# M961.net
KiCad netlist of a schematic drawn in EAGLE
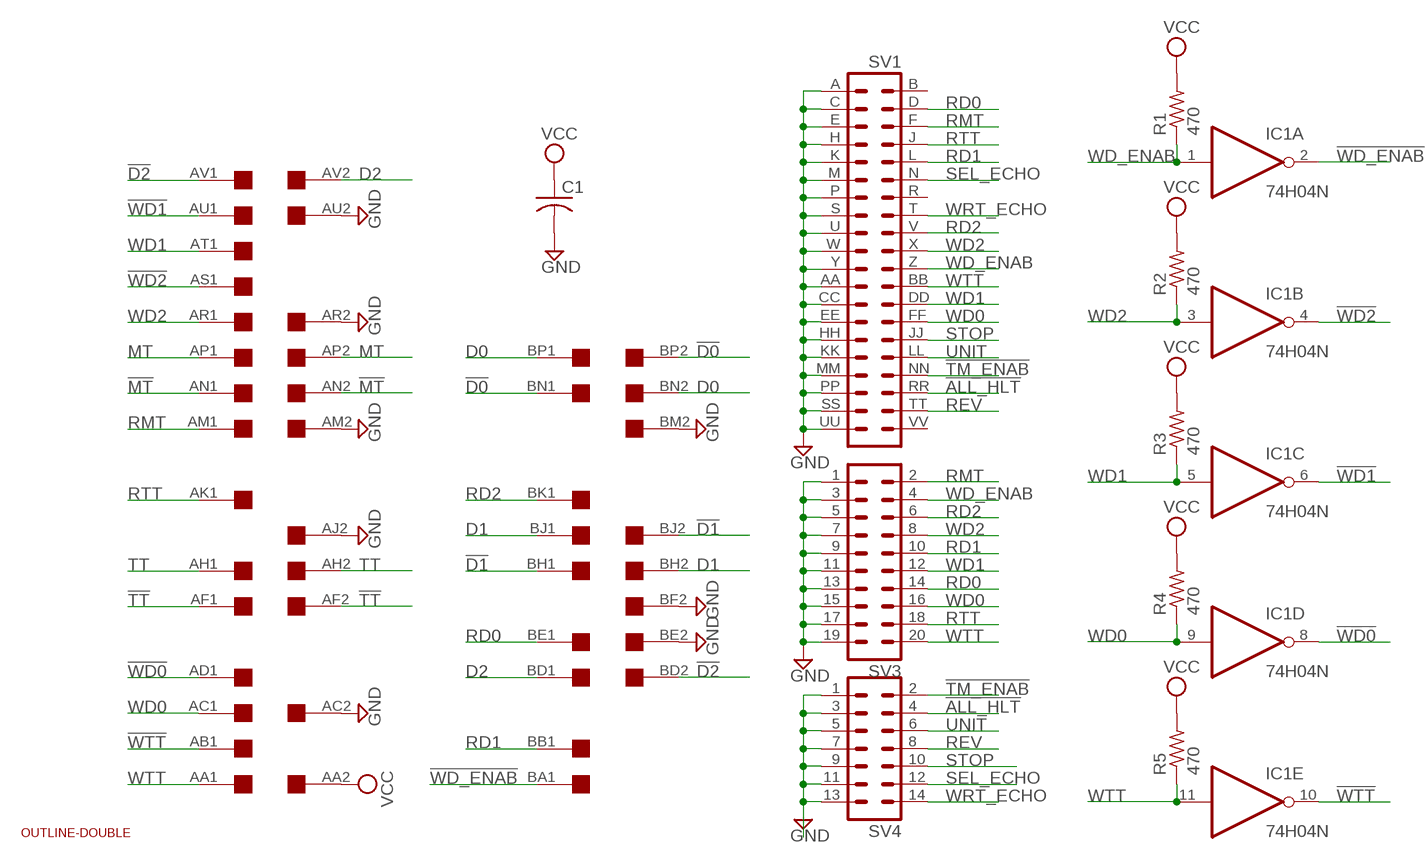
[diagram p0: schematic, sheet 1]

(export (version "E")
  (design (tool "Eeschema 10.0.6"))
  (components
    (comp (ref "C1")
      (value "C-US050-025X075")
      (footprint "eagle-import:C050-025X075")
      (libsource (lib "eagle-import") (part "C-US050-025X075"))
    )
    (comp (ref "EDGE$1")
      (value "DOUBLE")
      (footprint "eagle-import:EDGE-CON4")
      (libsource (lib "eagle-import") (part "DOUBLE"))
    )
    (comp (ref "IC1")
      (value "74H04N")
      (footprint "eagle-import:DIL14")
      (libsource (lib "eagle-import") (part "7404N"))
    )
    (comp (ref "R1")
      (value "470")
      (footprint "eagle-import:0207_10")
      (libsource (lib "eagle-import") (part "R-US_0207/10"))
    )
    (comp (ref "R2")
      (value "470")
      (footprint "eagle-import:0207_10")
      (libsource (lib "eagle-import") (part "R-US_0207/10"))
    )
    (comp (ref "R3")
      (value "470")
      (footprint "eagle-import:0207_10")
      (libsource (lib "eagle-import") (part "R-US_0207/10"))
    )
    (comp (ref "R4")
      (value "470")
      (footprint "eagle-import:0207_10")
      (libsource (lib "eagle-import") (part "R-US_0207/10"))
    )
    (comp (ref "R5")
      (value "470")
      (footprint "eagle-import:0207_10")
      (libsource (lib "eagle-import") (part "R-US_0207/10"))
    )
    (comp (ref "SV1")
      (value "DEC40PINV")
      (footprint "eagle-import:DEC40PINV")
      (libsource (lib "eagle-import") (part "DEC40PINV"))
    )
    (comp (ref "SV3")
      (value "MA10-2")
      (footprint "eagle-import:MA10-2")
      (libsource (lib "eagle-import") (part "MA10-2"))
    )
    (comp (ref "SV4")
      (value "MA07-2")
      (footprint "eagle-import:MA07-2")
      (libsource (lib "eagle-import") (part "MA07-2"))
    )
    (comp (ref "U$2")
      (value "OUTLINE-DOUBLE")
      (footprint "eagle-import:DOUBLE")
      (libsource (lib "eagle-import") (part "OUTLINE-DOUBLE"))
    )
  )
  (nets
    (net (code "1") (name "/D0") (class "Default")
      (node (ref "EDGE$1") (pin "BN2") (pinfunction "1_BN2") (pintype "bidirectional"))
      (node (ref "EDGE$1") (pin "BP1") (pinfunction "1_BP1") (pintype "bidirectional"))
    )
    (net (code "2") (name "/D1") (class "Default")
      (node (ref "EDGE$1") (pin "BH2") (pinfunction "1_BH2") (pintype "bidirectional"))
      (node (ref "EDGE$1") (pin "BJ1") (pinfunction "1_BJ1") (pintype "bidirectional"))
    )
    (net (code "3") (name "/D2") (class "Default")
      (node (ref "EDGE$1") (pin "AV2") (pinfunction "1_AV2") (pintype "bidirectional"))
      (node (ref "EDGE$1") (pin "BD1") (pinfunction "1_BD1") (pintype "bidirectional"))
    )
    (net (code "4") (name "/MT") (class "Default")
      (node (ref "EDGE$1") (pin "AP1") (pinfunction "1_AP1") (pintype "bidirectional"))
      (node (ref "EDGE$1") (pin "AP2") (pinfunction "1_AP2") (pintype "bidirectional"))
    )
    (net (code "5") (name "/RD0") (class "Default")
      (node (ref "EDGE$1") (pin "BE1") (pinfunction "1_BE1") (pintype "bidirectional"))
      (node (ref "SV1") (pin "D") (pinfunction "4_D") (pintype "bidirectional"))
      (node (ref "SV3") (pin "14") (pinfunction "14_14") (pintype "passive"))
    )
    (net (code "6") (name "/RD1") (class "Default")
      (node (ref "EDGE$1") (pin "BB1") (pinfunction "1_BB1") (pintype "bidirectional"))
      (node (ref "SV1") (pin "L") (pinfunction "10_L") (pintype "bidirectional"))
      (node (ref "SV3") (pin "10") (pinfunction "10_10") (pintype "passive"))
    )
    (net (code "7") (name "/RD2") (class "Default")
      (node (ref "EDGE$1") (pin "BK1") (pinfunction "1_BK1") (pintype "bidirectional"))
      (node (ref "SV1") (pin "V") (pinfunction "18_V") (pintype "bidirectional"))
      (node (ref "SV3") (pin "6") (pinfunction "6_6") (pintype "passive"))
    )
    (net (code "8") (name "/REV") (class "Default")
      (node (ref "SV1") (pin "TT") (pinfunction "38_TT") (pintype "bidirectional"))
      (node (ref "SV4") (pin "8") (pinfunction "8_8") (pintype "passive"))
    )
    (net (code "9") (name "/RMT") (class "Default")
      (node (ref "EDGE$1") (pin "AM1") (pinfunction "1_AM1") (pintype "bidirectional"))
      (node (ref "SV1") (pin "F") (pinfunction "6_F") (pintype "bidirectional"))
      (node (ref "SV3") (pin "2") (pinfunction "2_2") (pintype "passive"))
    )
    (net (code "10") (name "/RTT") (class "Default")
      (node (ref "EDGE$1") (pin "AK1") (pinfunction "1_AK1") (pintype "bidirectional"))
      (node (ref "SV1") (pin "J") (pinfunction "8_J") (pintype "bidirectional"))
      (node (ref "SV3") (pin "18") (pinfunction "18_18") (pintype "passive"))
    )
    (net (code "11") (name "/SEL_ECHO") (class "Default")
      (node (ref "SV1") (pin "N") (pinfunction "12_N") (pintype "bidirectional"))
      (node (ref "SV4") (pin "12") (pinfunction "12_12") (pintype "passive"))
    )
    (net (code "12") (name "/STOP") (class "Default")
      (node (ref "SV1") (pin "JJ") (pinfunction "30_JJ") (pintype "bidirectional"))
      (node (ref "SV4") (pin "10") (pinfunction "10_10") (pintype "passive"))
    )
    (net (code "13") (name "/TT") (class "Default")
      (node (ref "EDGE$1") (pin "AH1") (pinfunction "1_AH1") (pintype "bidirectional"))
      (node (ref "EDGE$1") (pin "AH2") (pinfunction "1_AH2") (pintype "bidirectional"))
    )
    (net (code "14") (name "/UNIT") (class "Default")
      (node (ref "SV1") (pin "LL") (pinfunction "32_LL") (pintype "bidirectional"))
      (node (ref "SV4") (pin "6") (pinfunction "6_6") (pintype "passive"))
    )
    (net (code "15") (name "/WD0") (class "Default")
      (node (ref "EDGE$1") (pin "AC1") (pinfunction "1_AC1") (pintype "bidirectional"))
      (node (ref "IC1") (pin "9") (pinfunction "I_9") (pintype "input"))
      (node (ref "R4") (pin "1") (pinfunction "1_1") (pintype "passive"))
      (node (ref "SV1") (pin "FF") (pinfunction "28_FF") (pintype "bidirectional"))
      (node (ref "SV3") (pin "16") (pinfunction "16_16") (pintype "passive"))
    )
    (net (code "16") (name "/WD1") (class "Default")
      (node (ref "EDGE$1") (pin "AT1") (pinfunction "1_AT1") (pintype "bidirectional"))
      (node (ref "IC1") (pin "5") (pinfunction "I_5") (pintype "input"))
      (node (ref "R3") (pin "1") (pinfunction "1_1") (pintype "passive"))
      (node (ref "SV1") (pin "DD") (pinfunction "26_DD") (pintype "bidirectional"))
      (node (ref "SV3") (pin "12") (pinfunction "12_12") (pintype "passive"))
    )
    (net (code "17") (name "/WD2") (class "Default")
      (node (ref "EDGE$1") (pin "AR1") (pinfunction "1_AR1") (pintype "bidirectional"))
      (node (ref "IC1") (pin "3") (pinfunction "I_3") (pintype "input"))
      (node (ref "R2") (pin "1") (pinfunction "1_1") (pintype "passive"))
      (node (ref "SV1") (pin "X") (pinfunction "20_X") (pintype "bidirectional"))
      (node (ref "SV3") (pin "8") (pinfunction "8_8") (pintype "passive"))
    )
    (net (code "18") (name "/WD_ENAB") (class "Default")
      (node (ref "IC1") (pin "1") (pinfunction "I_1") (pintype "input"))
      (node (ref "R1") (pin "1") (pinfunction "1_1") (pintype "passive"))
      (node (ref "SV1") (pin "Z") (pinfunction "22_Z") (pintype "bidirectional"))
      (node (ref "SV3") (pin "4") (pinfunction "4_4") (pintype "passive"))
    )
    (net (code "19") (name "/WRT_ECHO") (class "Default")
      (node (ref "SV1") (pin "T") (pinfunction "16_T") (pintype "bidirectional"))
      (node (ref "SV4") (pin "14") (pinfunction "14_14") (pintype "passive"))
    )
    (net (code "20") (name "/WTT") (class "Default")
      (node (ref "EDGE$1") (pin "AA1") (pinfunction "1_AA1") (pintype "bidirectional"))
      (node (ref "IC1") (pin "11") (pinfunction "I_11") (pintype "input"))
      (node (ref "R5") (pin "1") (pinfunction "1_1") (pintype "passive"))
      (node (ref "SV1") (pin "BB") (pinfunction "24_BB") (pintype "bidirectional"))
      (node (ref "SV3") (pin "20") (pinfunction "20_20") (pintype "passive"))
    )
    (net (code "21") (name "/~{ALL_HLT}") (class "Default")
      (node (ref "SV1") (pin "RR") (pinfunction "36_RR") (pintype "bidirectional"))
      (node (ref "SV4") (pin "4") (pinfunction "4_4") (pintype "passive"))
    )
    (net (code "22") (name "/~{D0}") (class "Default")
      (node (ref "EDGE$1") (pin "BN1") (pinfunction "1_BN1") (pintype "bidirectional"))
      (node (ref "EDGE$1") (pin "BP2") (pinfunction "1_BP2") (pintype "bidirectional"))
    )
    (net (code "23") (name "/~{D1}") (class "Default")
      (node (ref "EDGE$1") (pin "BH1") (pinfunction "1_BH1") (pintype "bidirectional"))
      (node (ref "EDGE$1") (pin "BJ2") (pinfunction "1_BJ2") (pintype "bidirectional"))
    )
    (net (code "24") (name "/~{D2}") (class "Default")
      (node (ref "EDGE$1") (pin "AV1") (pinfunction "1_AV1") (pintype "bidirectional"))
      (node (ref "EDGE$1") (pin "BD2") (pinfunction "1_BD2") (pintype "bidirectional"))
    )
    (net (code "25") (name "/~{MT}") (class "Default")
      (node (ref "EDGE$1") (pin "AN1") (pinfunction "1_AN1") (pintype "bidirectional"))
      (node (ref "EDGE$1") (pin "AN2") (pinfunction "1_AN2") (pintype "bidirectional"))
    )
    (net (code "26") (name "/~{TM_ENAB}") (class "Default")
      (node (ref "SV1") (pin "NN") (pinfunction "34_NN") (pintype "bidirectional"))
      (node (ref "SV4") (pin "2") (pinfunction "2_2") (pintype "passive"))
    )
    (net (code "27") (name "/~{TT}") (class "Default")
      (node (ref "EDGE$1") (pin "AF1") (pinfunction "1_AF1") (pintype "bidirectional"))
      (node (ref "EDGE$1") (pin "AF2") (pinfunction "1_AF2") (pintype "bidirectional"))
    )
    (net (code "28") (name "/~{WD0}") (class "Default")
      (node (ref "EDGE$1") (pin "AD1") (pinfunction "1_AD1") (pintype "bidirectional"))
      (node (ref "IC1") (pin "8") (pinfunction "O_8") (pintype "output"))
    )
    (net (code "29") (name "/~{WD1}") (class "Default")
      (node (ref "EDGE$1") (pin "AU1") (pinfunction "1_AU1") (pintype "bidirectional"))
      (node (ref "IC1") (pin "6") (pinfunction "O_6") (pintype "output"))
    )
    (net (code "30") (name "/~{WD2}") (class "Default")
      (node (ref "EDGE$1") (pin "AS1") (pinfunction "1_AS1") (pintype "bidirectional"))
      (node (ref "IC1") (pin "4") (pinfunction "O_4") (pintype "output"))
    )
    (net (code "31") (name "/~{WD_ENAB}") (class "Default")
      (node (ref "EDGE$1") (pin "BA1") (pinfunction "1_BA1") (pintype "bidirectional"))
      (node (ref "IC1") (pin "2") (pinfunction "O_2") (pintype "output"))
    )
    (net (code "32") (name "/~{WTT}") (class "Default")
      (node (ref "EDGE$1") (pin "AB1") (pinfunction "1_AB1") (pintype "bidirectional"))
      (node (ref "IC1") (pin "10") (pinfunction "O_10") (pintype "output"))
    )
    (net (code "33") (name "GND") (class "Default")
      (node (ref "C1") (pin "2") (pinfunction "2_2") (pintype "passive"))
      (node (ref "EDGE$1") (pin "AC2") (pinfunction "1_AC2") (pintype "bidirectional"))
      (node (ref "EDGE$1") (pin "AJ2") (pinfunction "1_AJ2") (pintype "bidirectional"))
      (node (ref "EDGE$1") (pin "AM2") (pinfunction "1_AM2") (pintype "bidirectional"))
      (node (ref "EDGE$1") (pin "AR2") (pinfunction "1_AR2") (pintype "bidirectional"))
      (node (ref "EDGE$1") (pin "AU2") (pinfunction "1_AU2") (pintype "bidirectional"))
      (node (ref "EDGE$1") (pin "BE2") (pinfunction "1_BE2") (pintype "bidirectional"))
      (node (ref "EDGE$1") (pin "BF2") (pinfunction "1_BF2") (pintype "bidirectional"))
      (node (ref "EDGE$1") (pin "BM2") (pinfunction "1_BM2") (pintype "bidirectional"))
      (node (ref "SV1") (pin "A") (pinfunction "1_A") (pintype "bidirectional"))
      (node (ref "SV1") (pin "AA") (pinfunction "23_AA") (pintype "bidirectional"))
      (node (ref "SV1") (pin "C") (pinfunction "3_C") (pintype "bidirectional"))
      (node (ref "SV1") (pin "CC") (pinfunction "25_CC") (pintype "bidirectional"))
      (node (ref "SV1") (pin "E") (pinfunction "5_E") (pintype "bidirectional"))
      (node (ref "SV1") (pin "EE") (pinfunction "27_EE") (pintype "bidirectional"))
      (node (ref "SV1") (pin "H") (pinfunction "7_H") (pintype "bidirectional"))
      (node (ref "SV1") (pin "HH") (pinfunction "29_HH") (pintype "bidirectional"))
      (node (ref "SV1") (pin "K") (pinfunction "9_K") (pintype "bidirectional"))
      (node (ref "SV1") (pin "KK") (pinfunction "31_KK") (pintype "bidirectional"))
      (node (ref "SV1") (pin "M") (pinfunction "11_M") (pintype "bidirectional"))
      (node (ref "SV1") (pin "MM") (pinfunction "33_MM") (pintype "bidirectional"))
      (node (ref "SV1") (pin "P") (pinfunction "13_P") (pintype "bidirectional"))
      (node (ref "SV1") (pin "PP") (pinfunction "35_PP") (pintype "bidirectional"))
      (node (ref "SV1") (pin "S") (pinfunction "15_S") (pintype "bidirectional"))
      (node (ref "SV1") (pin "SS") (pinfunction "37_SS") (pintype "bidirectional"))
      (node (ref "SV1") (pin "U") (pinfunction "17_U") (pintype "bidirectional"))
      (node (ref "SV1") (pin "UU") (pinfunction "39_UU") (pintype "bidirectional"))
      (node (ref "SV1") (pin "W") (pinfunction "19_W") (pintype "bidirectional"))
      (node (ref "SV1") (pin "Y") (pinfunction "21_Y") (pintype "bidirectional"))
      (node (ref "SV3") (pin "1") (pinfunction "1_1") (pintype "passive"))
      (node (ref "SV3") (pin "11") (pinfunction "11_11") (pintype "passive"))
      (node (ref "SV3") (pin "13") (pinfunction "13_13") (pintype "passive"))
      (node (ref "SV3") (pin "15") (pinfunction "15_15") (pintype "passive"))
      (node (ref "SV3") (pin "17") (pinfunction "17_17") (pintype "passive"))
      (node (ref "SV3") (pin "19") (pinfunction "19_19") (pintype "passive"))
      (node (ref "SV3") (pin "3") (pinfunction "3_3") (pintype "passive"))
      (node (ref "SV3") (pin "5") (pinfunction "5_5") (pintype "passive"))
      (node (ref "SV3") (pin "7") (pinfunction "7_7") (pintype "passive"))
      (node (ref "SV3") (pin "9") (pinfunction "9_9") (pintype "passive"))
      (node (ref "SV4") (pin "1") (pinfunction "1_1") (pintype "passive"))
      (node (ref "SV4") (pin "11") (pinfunction "11_11") (pintype "passive"))
      (node (ref "SV4") (pin "13") (pinfunction "13_13") (pintype "passive"))
      (node (ref "SV4") (pin "3") (pinfunction "3_3") (pintype "passive"))
      (node (ref "SV4") (pin "5") (pinfunction "5_5") (pintype "passive"))
      (node (ref "SV4") (pin "7") (pinfunction "7_7") (pintype "passive"))
      (node (ref "SV4") (pin "9") (pinfunction "9_9") (pintype "passive"))
    )
    (net (code "34") (name "VCC") (class "Default")
      (node (ref "C1") (pin "1") (pinfunction "1_1") (pintype "passive"))
      (node (ref "EDGE$1") (pin "AA2") (pinfunction "1_AA2") (pintype "bidirectional"))
      (node (ref "R1") (pin "2") (pinfunction "2_2") (pintype "passive"))
      (node (ref "R2") (pin "2") (pinfunction "2_2") (pintype "passive"))
      (node (ref "R3") (pin "2") (pinfunction "2_2") (pintype "passive"))
      (node (ref "R4") (pin "2") (pinfunction "2_2") (pintype "passive"))
      (node (ref "R5") (pin "2") (pinfunction "2_2") (pintype "passive"))
    )
    (net (code "35") (name "unconnected-(SV1-2-PadB)") (class "Default")
      (node (ref "SV1") (pin "B") (pinfunction "2_B") (pintype "bidirectional"))
    )
    (net (code "36") (name "unconnected-(SV1-14-PadR)") (class "Default")
      (node (ref "SV1") (pin "R") (pinfunction "14_R") (pintype "bidirectional"))
    )
    (net (code "37") (name "unconnected-(SV1-40-PadVV)") (class "Default")
      (node (ref "SV1") (pin "VV") (pinfunction "40_VV") (pintype "bidirectional"))
    )
  )
)
